# Top.net
KiCad netlist of a schematic drawn in Altium Designer
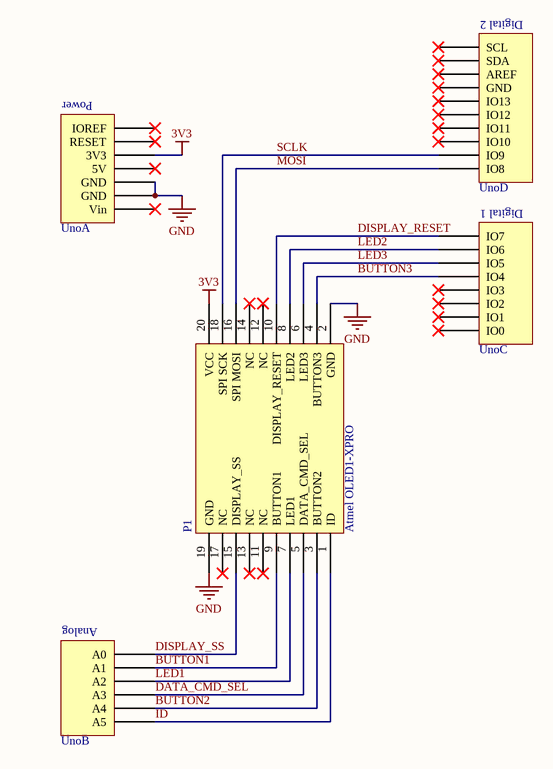
[diagram p0: Top.SchDoc]

(export (version "E")
  (design (tool "Eeschema 10.0.6"))
  (components
    (comp (ref "P1") (value "Atmel OLED1-XPRO") (libsource (lib "Headers") (part "Atmel OLED1-XPRO")))
    (comp (ref "Uno")
      (value "Arduino Uno Shield")
      (footprint "Arduino Uno Shield")
      (libsource (lib "Arduino") (part "Arduino Uno"))
    )
  )
  (nets
    (net (code "1") (name "/BUTTON1") (class "Default")
      (node (ref "P1") (pin "9") (pinfunction "BUTTON1_9") (pintype "passive"))
      (node (ref "Uno") (pin "A1") (pinfunction "A1_A1") (pintype "passive"))
    )
    (net (code "2") (name "/BUTTON2") (class "Default")
      (node (ref "P1") (pin "3") (pinfunction "BUTTON2_3") (pintype "passive"))
      (node (ref "Uno") (pin "A4") (pinfunction "A4_A4") (pintype "passive"))
    )
    (net (code "3") (name "/BUTTON3") (class "Default")
      (node (ref "P1") (pin "4") (pinfunction "BUTTON3_4") (pintype "passive"))
      (node (ref "Uno") (pin "4") (pinfunction "IO4_4") (pintype "passive"))
    )
    (net (code "4") (name "/DATA_CMD_SEL") (class "Default")
      (node (ref "P1") (pin "5") (pinfunction "DATA_CMD_SEL_5") (pintype "passive"))
      (node (ref "Uno") (pin "A3") (pinfunction "A3_A3") (pintype "passive"))
    )
    (net (code "5") (name "/DISPLAY_RESET") (class "Default")
      (node (ref "P1") (pin "10") (pinfunction "DISPLAY_RESET_10") (pintype "passive"))
      (node (ref "Uno") (pin "7") (pinfunction "IO7_7") (pintype "passive"))
    )
    (net (code "6") (name "/DISPLAY_SS") (class "Default")
      (node (ref "P1") (pin "15") (pinfunction "DISPLAY_SS_15") (pintype "passive"))
      (node (ref "Uno") (pin "A0") (pinfunction "A0_A0") (pintype "passive"))
    )
    (net (code "7") (name "/ID") (class "Default")
      (node (ref "P1") (pin "1") (pinfunction "ID_1") (pintype "passive"))
      (node (ref "Uno") (pin "A5") (pinfunction "A5_A5") (pintype "passive"))
    )
    (net (code "8") (name "/LED1") (class "Default")
      (node (ref "P1") (pin "7") (pinfunction "LED1_7") (pintype "passive"))
      (node (ref "Uno") (pin "A2") (pinfunction "A2_A2") (pintype "passive"))
    )
    (net (code "9") (name "/LED2") (class "Default")
      (node (ref "P1") (pin "8") (pinfunction "LED2_8") (pintype "passive"))
      (node (ref "Uno") (pin "6") (pinfunction "IO6_6") (pintype "passive"))
    )
    (net (code "10") (name "/LED3") (class "Default")
      (node (ref "P1") (pin "6") (pinfunction "LED3_6") (pintype "passive"))
      (node (ref "Uno") (pin "5") (pinfunction "IO5_5") (pintype "passive"))
    )
    (net (code "11") (name "/MOSI") (class "Default")
      (node (ref "P1") (pin "16") (pinfunction "SPI_MOSI_16") (pintype "passive"))
      (node (ref "Uno") (pin "8") (pinfunction "IO8_8") (pintype "passive"))
    )
    (net (code "12") (name "/SCLK") (class "Default")
      (node (ref "P1") (pin "18") (pinfunction "SPI_SCK_18") (pintype "passive"))
      (node (ref "Uno") (pin "9") (pinfunction "IO9_9") (pintype "passive"))
    )
    (net (code "13") (name "3V3") (class "Default")
      (node (ref "P1") (pin "20") (pinfunction "VCC_20") (pintype "passive"))
      (node (ref "Uno") (pin "3V3") (pinfunction "3V3_3V3") (pintype "passive"))
    )
    (net (code "14") (name "GND") (class "Default")
      (node (ref "P1") (pin "19") (pinfunction "GND_19") (pintype "passive"))
      (node (ref "P1") (pin "2") (pinfunction "GND_2") (pintype "passive"))
      (node (ref "Uno") (pin "GND1") (pinfunction "GND_GND1") (pintype "passive"))
      (node (ref "Uno") (pin "GND2") (pinfunction "GND_GND2") (pintype "passive"))
    )
    (net (code "15") (name "unconnected-(P1-NC-Pad11)") (class "Default")
      (node (ref "P1") (pin "11") (pinfunction "NC_11") (pintype "passive+no_connect"))
    )
    (net (code "16") (name "unconnected-(P1-NC-Pad12)") (class "Default")
      (node (ref "P1") (pin "12") (pinfunction "NC_12") (pintype "passive+no_connect"))
    )
    (net (code "17") (name "unconnected-(P1-NC-Pad13)") (class "Default")
      (node (ref "P1") (pin "13") (pinfunction "NC_13") (pintype "passive+no_connect"))
    )
    (net (code "18") (name "unconnected-(P1-NC-Pad14)") (class "Default")
      (node (ref "P1") (pin "14") (pinfunction "NC_14") (pintype "passive+no_connect"))
    )
    (net (code "19") (name "unconnected-(P1-NC-Pad17)") (class "Default")
      (node (ref "P1") (pin "17") (pinfunction "NC_17") (pintype "passive+no_connect"))
    )
    (net (code "20") (name "unconnected-(Uno-Pad5V)") (class "Default")
      (node (ref "Uno") (pin "5V") (pinfunction "5V_5V") (pintype "passive+no_connect"))
    )
    (net (code "21") (name "unconnected-(Uno-PadAREF)") (class "Default")
      (node (ref "Uno") (pin "AREF") (pinfunction "AREF_AREF") (pintype "passive+no_connect"))
    )
    (net (code "22") (name "unconnected-(Uno-PadIOREF)") (class "Default")
      (node (ref "Uno") (pin "IOREF") (pinfunction "IOREF_IOREF") (pintype "passive+no_connect"))
    )
    (net (code "23") (name "unconnected-(Uno-PadRESET)") (class "Default")
      (node (ref "Uno") (pin "RESET") (pinfunction "RESET_RESET") (pintype "passive+no_connect"))
    )
    (net (code "24") (name "unconnected-(Uno-PadSCL)") (class "Default")
      (node (ref "Uno") (pin "SCL") (pinfunction "SCL_SCL") (pintype "passive+no_connect"))
    )
    (net (code "25") (name "unconnected-(Uno-PadSDA)") (class "Default")
      (node (ref "Uno") (pin "SDA") (pinfunction "SDA_SDA") (pintype "passive+no_connect"))
    )
    (net (code "26") (name "unconnected-(Uno-PadVin)") (class "Default")
      (node (ref "Uno") (pin "Vin") (pinfunction "Vin_Vin") (pintype "passive+no_connect"))
    )
    (net (code "27") (name "unconnected-(UnoC-IO0-Pad0)") (class "Default")
      (node (ref "Uno") (pin "0") (pinfunction "IO0_0") (pintype "passive+no_connect"))
    )
    (net (code "28") (name "unconnected-(UnoC-IO1-Pad1)") (class "Default")
      (node (ref "Uno") (pin "1") (pinfunction "IO1_1") (pintype "passive+no_connect"))
    )
    (net (code "29") (name "unconnected-(UnoC-IO2-Pad2)") (class "Default")
      (node (ref "Uno") (pin "2") (pinfunction "IO2_2") (pintype "passive+no_connect"))
    )
    (net (code "30") (name "unconnected-(UnoC-IO3-Pad3)") (class "Default")
      (node (ref "Uno") (pin "3") (pinfunction "IO3_3") (pintype "passive+no_connect"))
    )
    (net (code "31") (name "unconnected-(UnoD-GND-PadGND3)") (class "Default")
      (node (ref "Uno") (pin "GND3") (pinfunction "GND_GND3") (pintype "passive+no_connect"))
    )
    (net (code "32") (name "unconnected-(UnoD-IO10-Pad10)") (class "Default")
      (node (ref "Uno") (pin "10") (pinfunction "IO10_10") (pintype "passive+no_connect"))
    )
    (net (code "33") (name "unconnected-(UnoD-IO11-Pad11)") (class "Default")
      (node (ref "Uno") (pin "11") (pinfunction "IO11_11") (pintype "passive+no_connect"))
    )
    (net (code "34") (name "unconnected-(UnoD-IO12-Pad12)") (class "Default")
      (node (ref "Uno") (pin "12") (pinfunction "IO12_12") (pintype "passive+no_connect"))
    )
    (net (code "35") (name "unconnected-(UnoD-IO13-Pad13)") (class "Default")
      (node (ref "Uno") (pin "13") (pinfunction "IO13_13") (pintype "passive+no_connect"))
    )
  )
)
